# nodequad_shield_2022-03-13.net
KiCad netlist of a schematic drawn in Altium Designer
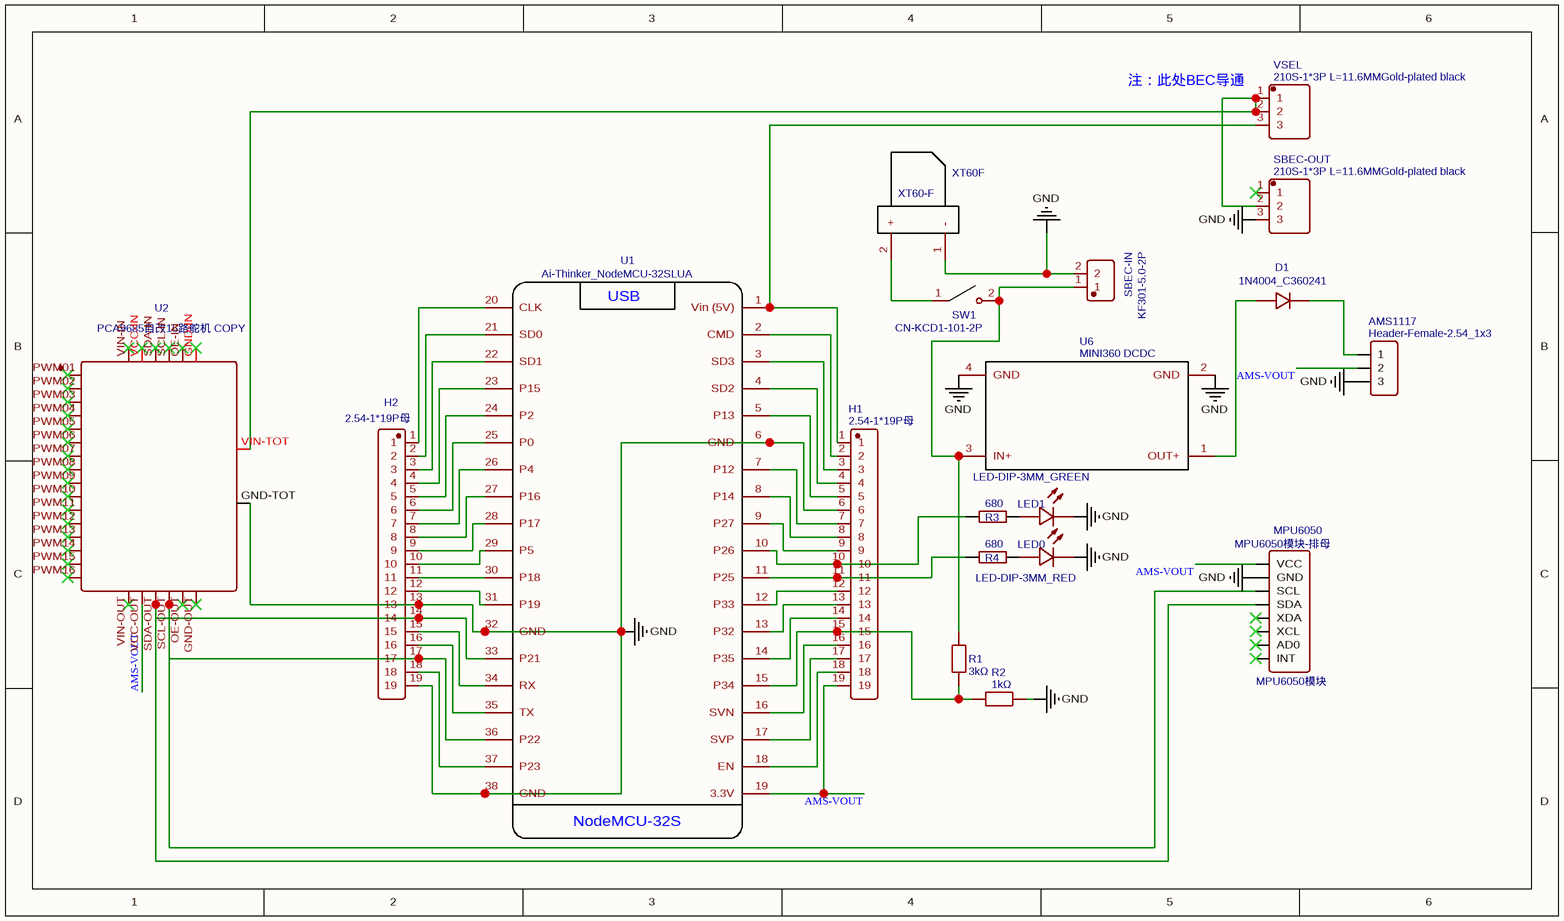
[diagram p0: nodequad_shield_2022-03-13.schdoc]

(export (version "E")
  (design (tool "Eeschema 10.0.6"))
  (components
    (comp (ref "AMS1117")
      (value "Header-Female-2.54_1x3")
      (fields (field (name "BOM_SUPPLIER PART") "C146243"))
      (libsource (lib "altium-import") (part "root_0_Header-Female-2.54_1x3_"))
    )
    (comp (ref "D1")
      (value "1N4004_C360241")
      (fields
        (field (name "BOM_SUPPLIER PART") "C360241")
        (field (name "BOM_MANUFACTURER PART") "1N4004")
        (field (name "CONTRIBUTOR") "LCSC")
      )
      (libsource (lib "altium-import") (part "root_2_1N4004_C360241_"))
    )
    (comp (ref "H1")
      (value "2.54-1*19P母")
      (fields (field (name "BOM_SUPPLIER PART") "C319202") (field (name "CONTRIBUTOR") "LCSC"))
      (libsource (lib "") (part "root_0_2.54-1*19P母__1"))
    )
    (comp (ref "H2")
      (value "2.54-1*19P母")
      (fields (field (name "BOM_SUPPLIER PART") "C319202") (field (name "CONTRIBUTOR") "LCSC"))
      (libsource (lib "altium-import") (part "root_0_2.54-1*19P母_"))
    )
    (comp (ref "LED0")
      (value "LED-DIP-3MM_RED")
      (fields
        (field (name "BOM_SUPPLIER PART") "C9900002364")
        (field (name "BOM_MANUFACTURER PART") "LED-DIP-3MM_Red")
        (field (name "CONTRIBUTOR") "LCSC")
      )
      (libsource (lib "altium-import") (part "root_0_LED-DIP-3MM_RED_"))
    )
    (comp (ref "LED1")
      (value "LED-DIP-3MM_GREEN")
      (fields
        (field (name "BOM_SUPPLIER PART") "C9900002365")
        (field (name "BOM_MANUFACTURER PART") "LED-DIP-3MM_Green")
        (field (name "CONTRIBUTOR") "LCSC")
      )
      (libsource (lib "altium-import") (part "root_0_LED-DIP-3MM_GREEN_"))
    )
    (comp (ref "MPU6050")
      (value "MPU6050模块-排母")
      (fields (field (name "CONTRIBUTOR") "W429367425"))
      (libsource (lib "altium-import") (part "root_0_MPU6050模块-排母_"))
    )
    (comp (ref "R1")
      (value "3kΩ")
      (fields
        (field (name "BOM_SUPPLIER PART") "C714005")
        (field (name "BOM_MANUFACTURER PART") "MF1/4W-3KΩ±1%T52")
        (field (name "CONTRIBUTOR") "LCSC")
      )
      (libsource (lib "altium-import") (part "root_1_3kΩ_"))
    )
    (comp (ref "R2")
      (value "1kΩ")
      (fields
        (field (name "BOM_SUPPLIER PART") "C713997")
        (field (name "BOM_MANUFACTURER PART") "MF1/4W-1KΩ±1%T52")
        (field (name "CONTRIBUTOR") "LCSC")
      )
      (libsource (lib "altium-import") (part "root_0_1kΩ_"))
    )
    (comp (ref "R3")
      (value "680")
      (fields (field (name "BOM_SUPPLIER PART") "C337184") (field (name "CONTRIBUTOR") "LCSC"))
      (libsource (lib "altium-import") (part "root_0_680_"))
    )
    (comp (ref "R4")
      (value "680")
      (fields (field (name "BOM_SUPPLIER PART") "C337184") (field (name "CONTRIBUTOR") "LCSC"))
      (libsource (lib "altium-import") (part "root_0_680_"))
    )
    (comp (ref "SBEC-IN")
      (value "KF301-5.0-2P")
      (fields (field (name "BOM_SUPPLIER PART") "C474881") (field (name "CONTRIBUTOR") "LCSC"))
      (libsource (lib "altium-import") (part "root_0_KF301-5.0-2P_"))
    )
    (comp (ref "SBEC-OUT")
      (value "210S-1*3P L=11.6MMGold-plated black")
      (fields (field (name "BOM_SUPPLIER PART") "C124376") (field (name "CONTRIBUTOR") "LCSC"))
      (libsource (lib "altium-import") (part "root_0_210S-1*3P L=11.6MMGold-plated black_"))
    )
    (comp (ref "SW1")
      (value "CN-KCD1-101-2P")
      (fields (field (name "BOM_SUPPLIER PART") "C9900002516") (field (name "CONTRIBUTOR") "LCSC"))
      (libsource (lib "altium-import") (part "root_0_CN-KCD1-101-2P_"))
    )
    (comp (ref "U1")
      (value "Ai-Thinker_NodeMCU-32SLUA")
      (fields
        (field (name "BOM_SUPPLIER PART") "C111436")
        (field (name "BOM_MANUFACTURER PART") "NodeMCU-32SLua")
        (field (name "CONTRIBUTOR") "jobsonp checked by LCSC")
      )
      (libsource (lib "altium-import") (part "root_2_Ai-Thinker_NodeMCU-32SLUA_"))
    )
    (comp (ref "U2")
      (value "PCA9685自改16路舵机 COPY")
      (fields
        (field (name "BOM_MANUFACTURER PART") "New SchematicLib")
        (field (name "CONTRIBUTOR") "hbyd110")
      )
      (libsource (lib "altium-import") (part "root_1_PCA9685自改16路舵机 COPY_"))
    )
    (comp (ref "U6")
      (value "MINI360 DCDC")
      (fields (field (name "CONTRIBUTOR") "libc0607"))
      (libsource (lib "altium-import") (part "root_2_MINI360 DCDC_"))
    )
    (comp (ref "VSEL")
      (value "210S-1*3P L=11.6MMGold-plated black")
      (fields (field (name "BOM_SUPPLIER PART") "C124376") (field (name "CONTRIBUTOR") "LCSC"))
      (libsource (lib "altium-import") (part "root_0_210S-1*3P L=11.6MMGold-plated black_"))
    )
    (comp (ref "XT60F")
      (value "XT60-F")
      (fields (field (name "CONTRIBUTOR") "ZhangYonghui"))
      (libsource (lib "altium-import") (part "root_0_XT60-F_"))
    )
  )
  (nets
    (net (code "1") (name "/AMS-VOUT") (class "Default")
      (node (ref "AMS1117") (pin "2") (pinfunction "2_2") (pintype "passive"))
      (node (ref "H1") (pin "19") (pinfunction "19_19") (pintype "passive"))
      (node (ref "MPU6050") (pin "1") (pinfunction "VCC_1") (pintype "passive"))
      (node (ref "U1") (pin "19") (pinfunction "3.3V_19") (pintype "passive"))
      (node (ref "U2") (pin "VCC-OUT") (pinfunction "1_VCC-OUT") (pintype "passive"))
    )
    (net (code "2") (name "GND") (class "Default")
      (node (ref "AMS1117") (pin "3") (pinfunction "3_3") (pintype "passive"))
      (node (ref "H1") (pin "6") (pinfunction "6_6") (pintype "passive"))
      (node (ref "H2") (pin "13") (pinfunction "13_13") (pintype "passive"))
      (node (ref "H2") (pin "19") (pinfunction "19_19") (pintype "passive"))
      (node (ref "LED0") (pin "1") (pinfunction "1_1") (pintype "passive"))
      (node (ref "LED1") (pin "1") (pinfunction "1_1") (pintype "passive"))
      (node (ref "MPU6050") (pin "2") (pinfunction "GND_2") (pintype "passive"))
      (node (ref "R2") (pin "2") (pinfunction "2_2") (pintype "passive"))
      (node (ref "SBEC-IN") (pin "2") (pinfunction "2_2") (pintype "passive"))
      (node (ref "SBEC-OUT") (pin "3") (pinfunction "3_3") (pintype "passive"))
      (node (ref "U1") (pin "32") (pinfunction "GND_32") (pintype "passive"))
      (node (ref "U1") (pin "38") (pinfunction "GND_38") (pintype "passive"))
      (node (ref "U1") (pin "6") (pinfunction "GND_6") (pintype "passive"))
      (node (ref "U2") (pin "GND-TOT") (pinfunction "GND_GND-TOT") (pintype "passive"))
      (node (ref "U6") (pin "2") (pinfunction "GND_2") (pintype "passive"))
      (node (ref "U6") (pin "4") (pinfunction "GND_4") (pintype "passive"))
      (node (ref "XT60F") (pin "1") (pinfunction "-_1") (pintype "passive"))
    )
    (net (code "3") (name "Net-(D1-+)") (class "Default")
      (node (ref "D1") (pin "2") (pinfunction "+_2") (pintype "passive"))
      (node (ref "U6") (pin "1") (pinfunction "OUT+_1") (pintype "passive"))
    )
    (net (code "4") (name "Net-(D1--)") (class "Default")
      (node (ref "AMS1117") (pin "1") (pinfunction "1_1") (pintype "passive"))
      (node (ref "D1") (pin "1") (pinfunction "-_1") (pintype "passive"))
    )
    (net (code "5") (name "Net-(LED0-Pad2)") (class "Default")
      (node (ref "LED0") (pin "2") (pinfunction "2_2") (pintype "passive"))
      (node (ref "R4") (pin "2") (pinfunction "2_2") (pintype "passive"))
    )
    (net (code "6") (name "Net-(LED1-Pad2)") (class "Default")
      (node (ref "LED1") (pin "2") (pinfunction "2_2") (pintype "passive"))
      (node (ref "R3") (pin "2") (pinfunction "2_2") (pintype "passive"))
    )
    (net (code "7") (name "Net-(MPU6050-SCL)") (class "Default")
      (node (ref "H2") (pin "17") (pinfunction "17_17") (pintype "passive"))
      (node (ref "MPU6050") (pin "3") (pinfunction "SCL_3") (pintype "passive"))
      (node (ref "U1") (pin "36") (pinfunction "P22_36") (pintype "passive"))
      (node (ref "U2") (pin "SCL-OUT") (pinfunction "1_SCL-OUT") (pintype "passive"))
    )
    (net (code "8") (name "Net-(MPU6050-SDA)") (class "Default")
      (node (ref "H2") (pin "14") (pinfunction "14_14") (pintype "passive"))
      (node (ref "MPU6050") (pin "4") (pinfunction "SDA_4") (pintype "passive"))
      (node (ref "U1") (pin "33") (pinfunction "P21_33") (pintype "passive"))
      (node (ref "U2") (pin "SDA-OUT") (pinfunction "1_SDA-OUT") (pintype "passive"))
    )
    (net (code "9") (name "Net-(U1-CLK)") (class "Default")
      (node (ref "H2") (pin "1") (pinfunction "1_1") (pintype "passive"))
      (node (ref "U1") (pin "20") (pinfunction "CLK_20") (pintype "passive"))
    )
    (net (code "10") (name "Net-(U1-CMD)") (class "Default")
      (node (ref "H1") (pin "2") (pinfunction "2_2") (pintype "passive"))
      (node (ref "U1") (pin "2") (pinfunction "CMD_2") (pintype "passive"))
    )
    (net (code "11") (name "Net-(U1-EN)") (class "Default")
      (node (ref "H1") (pin "18") (pinfunction "18_18") (pintype "passive"))
      (node (ref "U1") (pin "18") (pinfunction "EN_18") (pintype "passive"))
    )
    (net (code "12") (name "Net-(U1-P0)") (class "Default")
      (node (ref "H2") (pin "6") (pinfunction "6_6") (pintype "passive"))
      (node (ref "U1") (pin "25") (pinfunction "P0_25") (pintype "passive"))
    )
    (net (code "13") (name "Net-(U1-P2)") (class "Default")
      (node (ref "H2") (pin "5") (pinfunction "5_5") (pintype "passive"))
      (node (ref "U1") (pin "24") (pinfunction "P2_24") (pintype "passive"))
    )
    (net (code "14") (name "Net-(U1-P4)") (class "Default")
      (node (ref "H2") (pin "7") (pinfunction "7_7") (pintype "passive"))
      (node (ref "U1") (pin "26") (pinfunction "P4_26") (pintype "passive"))
    )
    (net (code "15") (name "Net-(U1-P5)") (class "Default")
      (node (ref "H2") (pin "10") (pinfunction "10_10") (pintype "passive"))
      (node (ref "U1") (pin "29") (pinfunction "P5_29") (pintype "passive"))
    )
    (net (code "16") (name "Net-(U1-P12)") (class "Default")
      (node (ref "H1") (pin "7") (pinfunction "7_7") (pintype "passive"))
      (node (ref "U1") (pin "7") (pinfunction "P12_7") (pintype "passive"))
    )
    (net (code "17") (name "Net-(U1-P13)") (class "Default")
      (node (ref "H1") (pin "5") (pinfunction "5_5") (pintype "passive"))
      (node (ref "U1") (pin "5") (pinfunction "P13_5") (pintype "passive"))
    )
    (net (code "18") (name "Net-(U1-P14)") (class "Default")
      (node (ref "H1") (pin "8") (pinfunction "8_8") (pintype "passive"))
      (node (ref "U1") (pin "8") (pinfunction "P14_8") (pintype "passive"))
    )
    (net (code "19") (name "Net-(U1-P15)") (class "Default")
      (node (ref "H2") (pin "4") (pinfunction "4_4") (pintype "passive"))
      (node (ref "U1") (pin "23") (pinfunction "P15_23") (pintype "passive"))
    )
    (net (code "20") (name "Net-(U1-P16)") (class "Default")
      (node (ref "H2") (pin "8") (pinfunction "8_8") (pintype "passive"))
      (node (ref "U1") (pin "27") (pinfunction "P16_27") (pintype "passive"))
    )
    (net (code "21") (name "Net-(U1-P17)") (class "Default")
      (node (ref "H2") (pin "9") (pinfunction "9_9") (pintype "passive"))
      (node (ref "U1") (pin "28") (pinfunction "P17_28") (pintype "passive"))
    )
    (net (code "22") (name "Net-(U1-P18)") (class "Default")
      (node (ref "H2") (pin "11") (pinfunction "11_11") (pintype "passive"))
      (node (ref "U1") (pin "30") (pinfunction "P18_30") (pintype "passive"))
    )
    (net (code "23") (name "Net-(U1-P19)") (class "Default")
      (node (ref "H2") (pin "12") (pinfunction "12_12") (pintype "passive"))
      (node (ref "U1") (pin "31") (pinfunction "P19_31") (pintype "passive"))
    )
    (net (code "24") (name "Net-(U1-P23)") (class "Default")
      (node (ref "H2") (pin "18") (pinfunction "18_18") (pintype "passive"))
      (node (ref "U1") (pin "37") (pinfunction "P23_37") (pintype "passive"))
    )
    (net (code "25") (name "Net-(U1-P25)") (class "Default")
      (node (ref "H1") (pin "11") (pinfunction "11_11") (pintype "passive"))
      (node (ref "R4") (pin "1") (pinfunction "1_1") (pintype "passive"))
      (node (ref "U1") (pin "11") (pinfunction "P25_11") (pintype "passive"))
    )
    (net (code "26") (name "Net-(U1-P26)") (class "Default")
      (node (ref "H1") (pin "10") (pinfunction "10_10") (pintype "passive"))
      (node (ref "R3") (pin "1") (pinfunction "1_1") (pintype "passive"))
      (node (ref "U1") (pin "10") (pinfunction "P26_10") (pintype "passive"))
    )
    (net (code "27") (name "Net-(U1-P27)") (class "Default")
      (node (ref "H1") (pin "9") (pinfunction "9_9") (pintype "passive"))
      (node (ref "U1") (pin "9") (pinfunction "P27_9") (pintype "passive"))
    )
    (net (code "28") (name "Net-(U1-P32)") (class "Default")
      (node (ref "H1") (pin "13") (pinfunction "13_13") (pintype "passive"))
      (node (ref "U1") (pin "13") (pinfunction "P32_13") (pintype "passive"))
    )
    (net (code "29") (name "Net-(U1-P33)") (class "Default")
      (node (ref "H1") (pin "12") (pinfunction "12_12") (pintype "passive"))
      (node (ref "U1") (pin "12") (pinfunction "P33_12") (pintype "passive"))
    )
    (net (code "30") (name "Net-(U1-P34)") (class "Default")
      (node (ref "H1") (pin "15") (pinfunction "15_15") (pintype "passive"))
      (node (ref "R1") (pin "1") (pinfunction "1_1") (pintype "passive"))
      (node (ref "R2") (pin "1") (pinfunction "1_1") (pintype "passive"))
      (node (ref "U1") (pin "15") (pinfunction "P34_15") (pintype "passive"))
    )
    (net (code "31") (name "Net-(U1-P35)") (class "Default")
      (node (ref "H1") (pin "14") (pinfunction "14_14") (pintype "passive"))
      (node (ref "U1") (pin "14") (pinfunction "P35_14") (pintype "passive"))
    )
    (net (code "32") (name "Net-(U1-RX)") (class "Default")
      (node (ref "H2") (pin "15") (pinfunction "15_15") (pintype "passive"))
      (node (ref "U1") (pin "34") (pinfunction "RX_34") (pintype "passive"))
    )
    (net (code "33") (name "Net-(U1-SD0)") (class "Default")
      (node (ref "H2") (pin "2") (pinfunction "2_2") (pintype "passive"))
      (node (ref "U1") (pin "21") (pinfunction "SD0_21") (pintype "passive"))
    )
    (net (code "34") (name "Net-(U1-SD1)") (class "Default")
      (node (ref "H2") (pin "3") (pinfunction "3_3") (pintype "passive"))
      (node (ref "U1") (pin "22") (pinfunction "SD1_22") (pintype "passive"))
    )
    (net (code "35") (name "Net-(U1-SD2)") (class "Default")
      (node (ref "H1") (pin "4") (pinfunction "4_4") (pintype "passive"))
      (node (ref "U1") (pin "4") (pinfunction "SD2_4") (pintype "passive"))
    )
    (net (code "36") (name "Net-(U1-SD3)") (class "Default")
      (node (ref "H1") (pin "3") (pinfunction "3_3") (pintype "passive"))
      (node (ref "U1") (pin "3") (pinfunction "SD3_3") (pintype "passive"))
    )
    (net (code "37") (name "Net-(U1-SVN)") (class "Default")
      (node (ref "H1") (pin "16") (pinfunction "16_16") (pintype "passive"))
      (node (ref "U1") (pin "16") (pinfunction "SVN_16") (pintype "passive"))
    )
    (net (code "38") (name "Net-(U1-SVP)") (class "Default")
      (node (ref "H1") (pin "17") (pinfunction "17_17") (pintype "passive"))
      (node (ref "U1") (pin "17") (pinfunction "SVP_17") (pintype "passive"))
    )
    (net (code "39") (name "Net-(U1-TX)") (class "Default")
      (node (ref "H2") (pin "16") (pinfunction "16_16") (pintype "passive"))
      (node (ref "U1") (pin "35") (pinfunction "TX_35") (pintype "passive"))
    )
    (net (code "40") (name "Net-(U1-Vin_(5V))") (class "Default")
      (node (ref "H1") (pin "1") (pinfunction "1_1") (pintype "passive"))
      (node (ref "U1") (pin "1") (pinfunction "Vin_(5V)_1") (pintype "passive"))
      (node (ref "VSEL") (pin "3") (pinfunction "3_3") (pintype "passive"))
    )
    (net (code "41") (name "Net-(U2-VPOWER)") (class "Default")
      (node (ref "SBEC-OUT") (pin "2") (pinfunction "2_2") (pintype "passive"))
      (node (ref "U2") (pin "VIN-TOT") (pinfunction "VPOWER_VIN-TOT") (pintype "passive"))
      (node (ref "VSEL") (pin "1") (pinfunction "1_1") (pintype "passive"))
      (node (ref "VSEL") (pin "2") (pinfunction "2_2") (pintype "passive"))
    )
    (net (code "42") (name "Net-(U6-IN+)") (class "Default")
      (node (ref "R1") (pin "2") (pinfunction "2_2") (pintype "passive"))
      (node (ref "SBEC-IN") (pin "1") (pinfunction "1_1") (pintype "passive"))
      (node (ref "SW1") (pin "2") (pinfunction "2_2") (pintype "passive"))
      (node (ref "U6") (pin "3") (pinfunction "IN+_3") (pintype "passive"))
    )
    (net (code "43") (name "Net-(XT60F-+)") (class "Default")
      (node (ref "SW1") (pin "1") (pinfunction "1_1") (pintype "passive"))
      (node (ref "XT60F") (pin "2") (pinfunction "+_2") (pintype "passive"))
    )
    (net (code "44") (name "unconnected-(MPU6050-AD0-Pad7)") (class "Default")
      (node (ref "MPU6050") (pin "7") (pinfunction "AD0_7") (pintype "passive+no_connect"))
    )
    (net (code "45") (name "unconnected-(MPU6050-INT-Pad8)") (class "Default")
      (node (ref "MPU6050") (pin "8") (pinfunction "INT_8") (pintype "passive+no_connect"))
    )
    (net (code "46") (name "unconnected-(MPU6050-XCL-Pad6)") (class "Default")
      (node (ref "MPU6050") (pin "6") (pinfunction "XCL_6") (pintype "passive+no_connect"))
    )
    (net (code "47") (name "unconnected-(MPU6050-XDA-Pad5)") (class "Default")
      (node (ref "MPU6050") (pin "5") (pinfunction "XDA_5") (pintype "passive+no_connect"))
    )
    (net (code "48") (name "unconnected-(SBEC-OUT-Pad1)") (class "Default")
      (node (ref "SBEC-OUT") (pin "1") (pinfunction "1_1") (pintype "passive+no_connect"))
    )
    (net (code "49") (name "unconnected-(U2-1-PadGND-OUT)") (class "Default")
      (node (ref "U2") (pin "GND-OUT") (pinfunction "1_GND-OUT") (pintype "passive+no_connect"))
    )
    (net (code "50") (name "unconnected-(U2-1-PadOE-OUT)") (class "Default")
      (node (ref "U2") (pin "OE-OUT") (pinfunction "1_OE-OUT") (pintype "passive+no_connect"))
    )
    (net (code "51") (name "unconnected-(U2-1-PadVIN-IN)") (class "Default")
      (node (ref "U2") (pin "VIN-IN") (pinfunction "1_VIN-IN") (pintype "passive+no_connect"))
    )
    (net (code "52") (name "unconnected-(U2-1-PadVIN-OUT)") (class "Default")
      (node (ref "U2") (pin "VIN-OUT") (pinfunction "1_VIN-OUT") (pintype "passive+no_connect"))
    )
    (net (code "53") (name "unconnected-(U2-2-PadOE-IN)") (class "Default")
      (node (ref "U2") (pin "OE-IN") (pinfunction "2_OE-IN") (pintype "passive+no_connect"))
    )
    (net (code "54") (name "unconnected-(U2-3-PadSCL-IN)") (class "Default")
      (node (ref "U2") (pin "SCL-IN") (pinfunction "3_SCL-IN") (pintype "passive+no_connect"))
    )
    (net (code "55") (name "unconnected-(U2-4-PadSDA-IN)") (class "Default")
      (node (ref "U2") (pin "SDA-IN") (pinfunction "4_SDA-IN") (pintype "passive+no_connect"))
    )
    (net (code "56") (name "unconnected-(U2-9-PadPWM01)") (class "Default")
      (node (ref "U2") (pin "PWM01") (pinfunction "9_PWM01") (pintype "passive+no_connect"))
    )
    (net (code "57") (name "unconnected-(U2-9-PadPWM02)") (class "Default")
      (node (ref "U2") (pin "PWM02") (pinfunction "9_PWM02") (pintype "passive+no_connect"))
    )
    (net (code "58") (name "unconnected-(U2-9-PadPWM03)") (class "Default")
      (node (ref "U2") (pin "PWM03") (pinfunction "9_PWM03") (pintype "passive+no_connect"))
    )
    (net (code "59") (name "unconnected-(U2-9-PadPWM04)") (class "Default")
      (node (ref "U2") (pin "PWM04") (pinfunction "9_PWM04") (pintype "passive+no_connect"))
    )
    (net (code "60") (name "unconnected-(U2-9-PadPWM05)") (class "Default")
      (node (ref "U2") (pin "PWM05") (pinfunction "9_PWM05") (pintype "passive+no_connect"))
    )
    (net (code "61") (name "unconnected-(U2-9-PadPWM06)") (class "Default")
      (node (ref "U2") (pin "PWM06") (pinfunction "9_PWM06") (pintype "passive+no_connect"))
    )
    (net (code "62") (name "unconnected-(U2-9-PadPWM07)") (class "Default")
      (node (ref "U2") (pin "PWM07") (pinfunction "9_PWM07") (pintype "passive+no_connect"))
    )
    (net (code "63") (name "unconnected-(U2-9-PadPWM08)") (class "Default")
      (node (ref "U2") (pin "PWM08") (pinfunction "9_PWM08") (pintype "passive+no_connect"))
    )
    (net (code "64") (name "unconnected-(U2-9-PadPWM09)") (class "Default")
      (node (ref "U2") (pin "PWM09") (pinfunction "9_PWM09") (pintype "passive+no_connect"))
    )
    (net (code "65") (name "unconnected-(U2-9-PadPWM10)") (class "Default")
      (node (ref "U2") (pin "PWM10") (pinfunction "9_PWM10") (pintype "passive+no_connect"))
    )
    (net (code "66") (name "unconnected-(U2-9-PadPWM11)") (class "Default")
      (node (ref "U2") (pin "PWM11") (pinfunction "9_PWM11") (pintype "passive+no_connect"))
    )
    (net (code "67") (name "unconnected-(U2-9-PadPWM12)") (class "Default")
      (node (ref "U2") (pin "PWM12") (pinfunction "9_PWM12") (pintype "passive+no_connect"))
    )
    (net (code "68") (name "unconnected-(U2-9-PadPWM13)") (class "Default")
      (node (ref "U2") (pin "PWM13") (pinfunction "9_PWM13") (pintype "passive+no_connect"))
    )
    (net (code "69") (name "unconnected-(U2-9-PadPWM14)") (class "Default")
      (node (ref "U2") (pin "PWM14") (pinfunction "9_PWM14") (pintype "passive+no_connect"))
    )
    (net (code "70") (name "unconnected-(U2-9-PadPWM15)") (class "Default")
      (node (ref "U2") (pin "PWM15") (pinfunction "9_PWM15") (pintype "passive+no_connect"))
    )
    (net (code "71") (name "unconnected-(U2-9-PadPWM16)") (class "Default")
      (node (ref "U2") (pin "PWM16") (pinfunction "9_PWM16") (pintype "passive+no_connect"))
    )
    (net (code "72") (name "unconnected-(U2-V+-PadGND-IN)") (class "Default")
      (node (ref "U2") (pin "GND-IN") (pinfunction "V+_GND-IN") (pintype "passive+no_connect"))
    )
    (net (code "73") (name "unconnected-(U2-VCC-PadVCC-IN)") (class "Default")
      (node (ref "U2") (pin "VCC-IN") (pinfunction "VCC_VCC-IN") (pintype "passive+no_connect"))
    )
  )
)
